# 8266_NFC_reader_added_power.net
KiCad netlist of a schematic drawn in EasyEDA
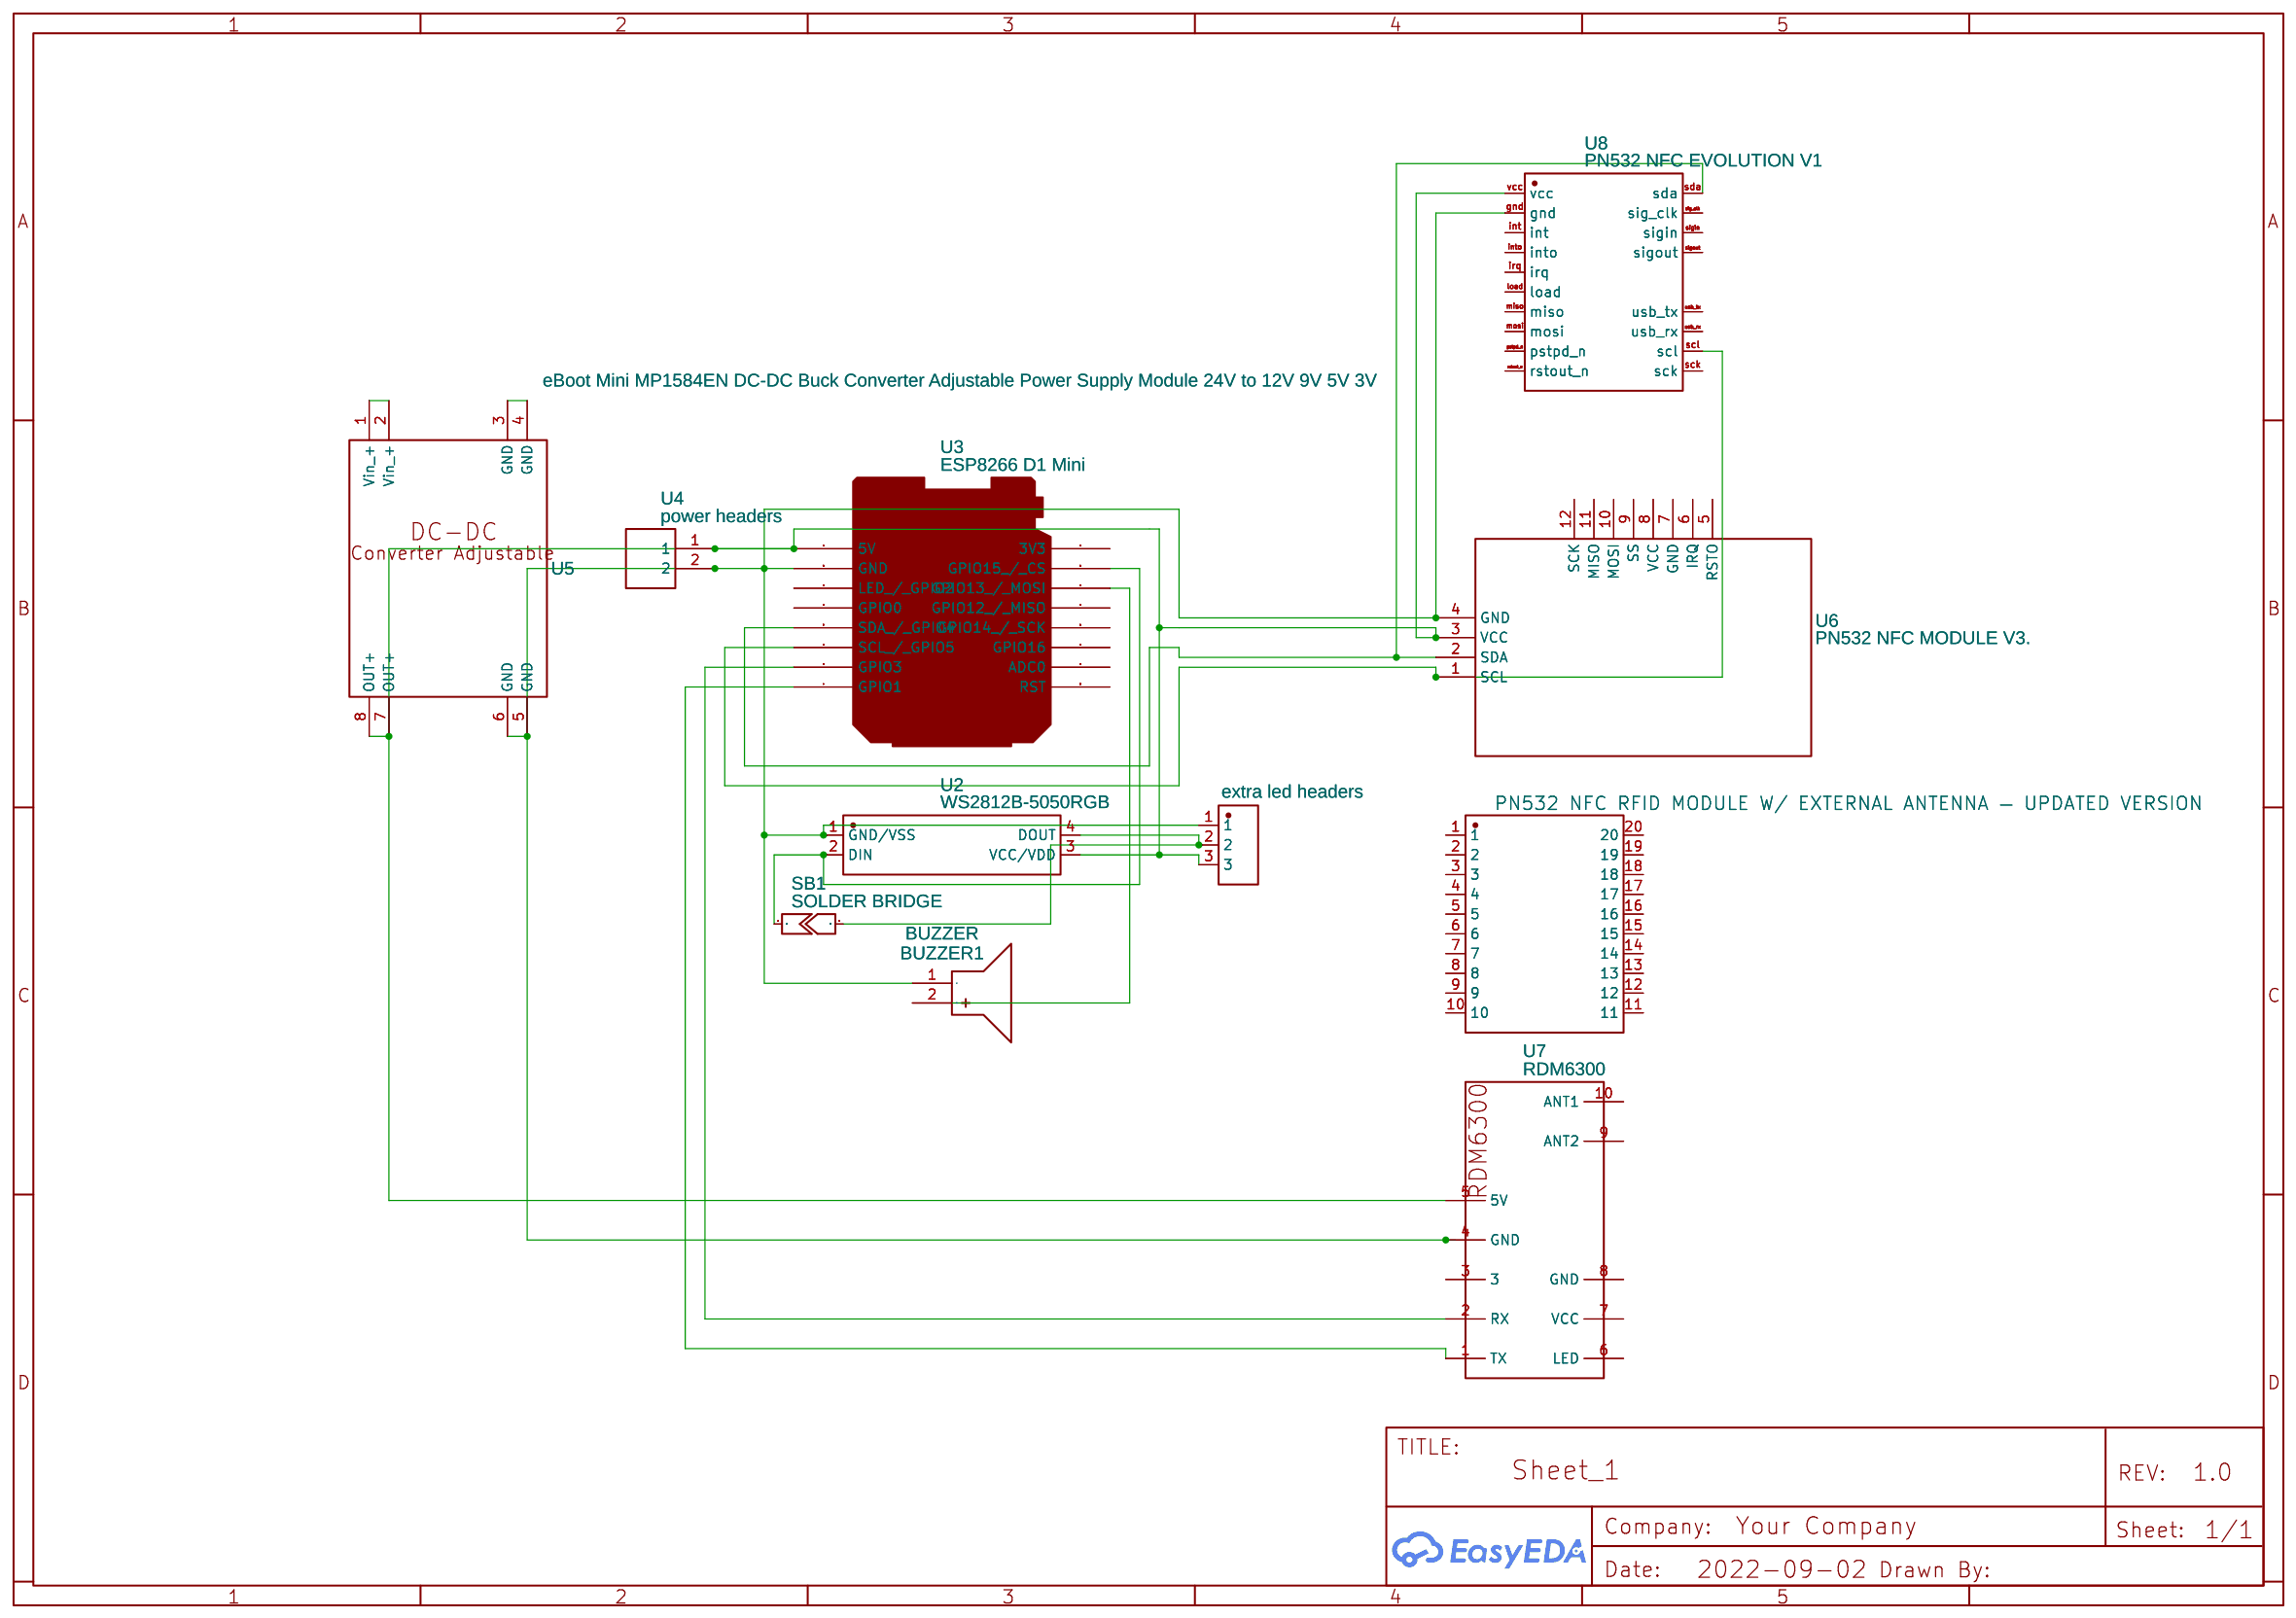
[diagram p0: schematic sheet]

(export (version "E")
  (design (tool "Eeschema 10.0.6"))
  (components
    (comp (ref "1")
      (value "extra led headers")
      (libsource (lib "") (part "PN532 NFC RFID MODULE W/ EXTERNAL ANTENNA — UPDATED VERSION"))
    )
    (comp (ref "BUZZER1")
      (value "BUZZER")
      (fields
        (field (name "BOM_Manufacturer Part") "buzzer")
        (field (name "BOM_Supplier Part") "C9900014030")
      )
      (libsource (lib "") (part "BUZZER"))
    )
    (comp (ref "SB1") (value "SOLDER BRIDGE") (libsource (lib "") (part "SOLDER BRIDGE")))
    (comp (ref "U2")
      (value "WS2812B-5050RGB")
      (fields (field (name "BOM_Supplier Part") "C2838584"))
      (libsource (lib "") (part "WS2812B-5050RGB"))
    )
    (comp (ref "U3") (value "ESP8266 D1 Mini") (libsource (lib "") (part "ESP8266 D1 Mini")))
    (comp (ref "U4")
      (value "power headers")
      (fields (field (name "BOM_Supplier Part") "7106"))
      (libsource (lib "") (part "1X2 HEADERS 2.54MM PITCH"))
    )
    (comp (ref "U5")
      (value "eBoot Mini MP1584EN DC-DC Buck Converter Adjustable Power Supply Module 24V to 12V 9V 5V 3V")
      (libsource (lib "") (part "eBoot Mini MP1584EN DC-DC Buck Converter Adjustable Power Supply Module 24V to 12V 9V 5V 3V"))
    )
    (comp (ref "U6") (value "PN532 NFC MODULE V3.") (libsource (lib "") (part "PN532 NFC MODULE V3.")))
    (comp (ref "U7") (value "RDM6300") (libsource (lib "") (part "RDM6300")))
    (comp (ref "U8") (value "PN532 NFC EVOLUTION V1") (libsource (lib "") (part "PN532 NFC EVOLUTION V1")))
  )
  (nets
    (net (code "1") (name "Net-(BUZZER1-+)") (class "Default")
      (node (ref "BUZZER1") (pin "2") (pinfunction "+_2") (pintype "unspecified"))
      (node (ref "U3") (pin "D7") (pinfunction "GPIO13_/_MOSI_D7") (pintype "bidirectional"))
    )
    (net (code "2") (name "Net-(BUZZER1--)") (class "Default")
      (node (ref "1") (pin "1") (pinfunction "1_1") (pintype "unspecified"))
      (node (ref "BUZZER1") (pin "1") (pinfunction "-_1") (pintype "unspecified"))
      (node (ref "U2") (pin "1") (pinfunction "GND/VSS_1") (pintype "unspecified"))
      (node (ref "U3") (pin "GND") (pinfunction "GND_GND") (pintype "passive"))
      (node (ref "U4") (pin "2") (pinfunction "2_2") (pintype "unspecified"))
      (node (ref "U5") (pin "5") (pinfunction "GND_5") (pintype "unspecified"))
      (node (ref "U5") (pin "6") (pinfunction "GND_6") (pintype "unspecified"))
      (node (ref "U6") (pin "4") (pinfunction "GND_4") (pintype "unspecified"))
      (node (ref "U7") (pin "4") (pinfunction "GND_4") (pintype "unspecified"))
      (node (ref "U8") (pin "gnd") (pinfunction "gnd_gnd") (pintype "unspecified"))
    )
    (net (code "3") (name "Net-(U2-DIN)") (class "Default")
      (node (ref "SB1") (pin "1") (pinfunction "1_1") (pintype "unspecified"))
      (node (ref "U2") (pin "2") (pinfunction "DIN_2") (pintype "unspecified"))
      (node (ref "U3") (pin "D8") (pinfunction "GPIO15_/_CS_D8") (pintype "bidirectional"))
    )
    (net (code "4") (name "Net-(U2-DOUT)") (class "Default")
      (node (ref "1") (pin "2") (pinfunction "2_2") (pintype "unspecified"))
      (node (ref "SB1") (pin "2") (pinfunction "2_2") (pintype "unspecified"))
      (node (ref "U2") (pin "4") (pinfunction "DOUT_4") (pintype "unspecified"))
    )
    (net (code "5") (name "Net-(U2-VCC{slash}VDD)") (class "Default")
      (node (ref "1") (pin "3") (pinfunction "3_3") (pintype "unspecified"))
      (node (ref "U2") (pin "3") (pinfunction "VCC/VDD_3") (pintype "unspecified"))
      (node (ref "U3") (pin "5V") (pinfunction "5V_5V") (pintype "passive"))
      (node (ref "U4") (pin "1") (pinfunction "1_1") (pintype "unspecified"))
      (node (ref "U5") (pin "7") (pinfunction "OUT+_7") (pintype "unspecified"))
      (node (ref "U5") (pin "8") (pinfunction "OUT+_8") (pintype "unspecified"))
      (node (ref "U6") (pin "3") (pinfunction "VCC_3") (pintype "unspecified"))
      (node (ref "U7") (pin "5") (pinfunction "5V_5") (pintype "unspecified"))
      (node (ref "U8") (pin "vcc") (pinfunction "vcc_vcc") (pintype "unspecified"))
    )
    (net (code "6") (name "Net-(U3-GPIO1)") (class "Default")
      (node (ref "U3") (pin "TX") (pinfunction "GPIO1_TX") (pintype "bidirectional"))
      (node (ref "U7") (pin "1") (pinfunction "TX_1") (pintype "unspecified"))
    )
    (net (code "7") (name "Net-(U3-GPIO3)") (class "Default")
      (node (ref "U3") (pin "RX") (pinfunction "GPIO3_RX") (pintype "bidirectional"))
      (node (ref "U7") (pin "2") (pinfunction "RX_2") (pintype "unspecified"))
    )
    (net (code "8") (name "Net-(U3-SCL_{slash}_GPIO5)") (class "Default")
      (node (ref "U3") (pin "D1") (pinfunction "SCL_/_GPIO5_D1") (pintype "bidirectional"))
      (node (ref "U6") (pin "1") (pinfunction "SCL_1") (pintype "unspecified"))
      (node (ref "U8") (pin "scl") (pinfunction "scl_scl") (pintype "unspecified"))
    )
    (net (code "9") (name "Net-(U3-SDA_{slash}_GPIO4)") (class "Default")
      (node (ref "U3") (pin "D2") (pinfunction "SDA_/_GPIO4_D2") (pintype "bidirectional"))
      (node (ref "U6") (pin "2") (pinfunction "SDA_2") (pintype "unspecified"))
      (node (ref "U8") (pin "sda") (pinfunction "sda_sda") (pintype "unspecified"))
    )
    (net (code "10") (name "Net-(U5-GND-Pad3)") (class "Default")
      (node (ref "U5") (pin "3") (pinfunction "GND_3") (pintype "unspecified"))
      (node (ref "U5") (pin "4") (pinfunction "GND_4") (pintype "unspecified"))
    )
    (net (code "11") (name "Net-(U5-Vin_+-Pad1)") (class "Default")
      (node (ref "U5") (pin "1") (pinfunction "Vin_+_1") (pintype "unspecified"))
      (node (ref "U5") (pin "2") (pinfunction "Vin_+_2") (pintype "unspecified"))
    )
    (net (code "12") (name "unconnected-(1-Pad1)") (class "Default")
      (node (ref "1") (pin "1") (pinfunction "1_1") (pintype "unspecified"))
    )
    (net (code "13") (name "unconnected-(1-Pad2)") (class "Default")
      (node (ref "1") (pin "2") (pinfunction "2_2") (pintype "unspecified"))
    )
    (net (code "14") (name "unconnected-(1-Pad3)") (class "Default")
      (node (ref "1") (pin "3") (pinfunction "3_3") (pintype "unspecified"))
    )
    (net (code "15") (name "unconnected-(1-Pad4)") (class "Default")
      (node (ref "1") (pin "4") (pinfunction "4_4") (pintype "unspecified"))
    )
    (net (code "16") (name "unconnected-(1-Pad5)") (class "Default")
      (node (ref "1") (pin "5") (pinfunction "5_5") (pintype "unspecified"))
    )
    (net (code "17") (name "unconnected-(1-Pad6)") (class "Default")
      (node (ref "1") (pin "6") (pinfunction "6_6") (pintype "unspecified"))
    )
    (net (code "18") (name "unconnected-(1-Pad7)") (class "Default")
      (node (ref "1") (pin "7") (pinfunction "7_7") (pintype "unspecified"))
    )
    (net (code "19") (name "unconnected-(1-Pad8)") (class "Default")
      (node (ref "1") (pin "8") (pinfunction "8_8") (pintype "unspecified"))
    )
    (net (code "20") (name "unconnected-(1-Pad9)") (class "Default")
      (node (ref "1") (pin "9") (pinfunction "9_9") (pintype "unspecified"))
    )
    (net (code "21") (name "unconnected-(1-Pad10)") (class "Default")
      (node (ref "1") (pin "10") (pinfunction "10_10") (pintype "unspecified"))
    )
    (net (code "22") (name "unconnected-(1-Pad11)") (class "Default")
      (node (ref "1") (pin "11") (pinfunction "11_11") (pintype "unspecified"))
    )
    (net (code "23") (name "unconnected-(1-Pad12)") (class "Default")
      (node (ref "1") (pin "12") (pinfunction "12_12") (pintype "unspecified"))
    )
    (net (code "24") (name "unconnected-(1-Pad13)") (class "Default")
      (node (ref "1") (pin "13") (pinfunction "13_13") (pintype "unspecified"))
    )
    (net (code "25") (name "unconnected-(1-Pad14)") (class "Default")
      (node (ref "1") (pin "14") (pinfunction "14_14") (pintype "unspecified"))
    )
    (net (code "26") (name "unconnected-(1-Pad15)") (class "Default")
      (node (ref "1") (pin "15") (pinfunction "15_15") (pintype "unspecified"))
    )
    (net (code "27") (name "unconnected-(1-Pad16)") (class "Default")
      (node (ref "1") (pin "16") (pinfunction "16_16") (pintype "unspecified"))
    )
    (net (code "28") (name "unconnected-(1-Pad17)") (class "Default")
      (node (ref "1") (pin "17") (pinfunction "17_17") (pintype "unspecified"))
    )
    (net (code "29") (name "unconnected-(1-Pad18)") (class "Default")
      (node (ref "1") (pin "18") (pinfunction "18_18") (pintype "unspecified"))
    )
    (net (code "30") (name "unconnected-(1-Pad19)") (class "Default")
      (node (ref "1") (pin "19") (pinfunction "19_19") (pintype "unspecified"))
    )
    (net (code "31") (name "unconnected-(1-Pad20)") (class "Default")
      (node (ref "1") (pin "20") (pinfunction "20_20") (pintype "unspecified"))
    )
    (net (code "32") (name "unconnected-(U3-ADC0-PadA0)") (class "Default")
      (node (ref "U3") (pin "A0") (pinfunction "ADC0_A0") (pintype "input"))
    )
    (net (code "33") (name "unconnected-(U3-GPIO0-PadD3)") (class "Default")
      (node (ref "U3") (pin "D3") (pinfunction "GPIO0_D3") (pintype "bidirectional"))
    )
    (net (code "34") (name "unconnected-(U3-GPIO12_{slash}_MISO-PadD6)") (class "Default")
      (node (ref "U3") (pin "D6") (pinfunction "GPIO12_/_MISO_D6") (pintype "bidirectional"))
    )
    (net (code "35") (name "unconnected-(U3-GPIO14_{slash}_SCK-PadD5)") (class "Default")
      (node (ref "U3") (pin "D5") (pinfunction "GPIO14_/_SCK_D5") (pintype "bidirectional"))
    )
    (net (code "36") (name "unconnected-(U3-GPIO16-PadD0)") (class "Default")
      (node (ref "U3") (pin "D0") (pinfunction "GPIO16_D0") (pintype "bidirectional"))
    )
    (net (code "37") (name "unconnected-(U3-LED_{slash}_GPIO2-PadD4)") (class "Default")
      (node (ref "U3") (pin "D4") (pinfunction "LED_/_GPIO2_D4") (pintype "bidirectional"))
    )
    (net (code "38") (name "unconnected-(U3-Pad3V3)") (class "Default")
      (node (ref "U3") (pin "3V3") (pinfunction "3V3_3V3") (pintype "passive"))
    )
    (net (code "39") (name "unconnected-(U3-PadRST)") (class "Default")
      (node (ref "U3") (pin "RST") (pinfunction "RST_RST") (pintype "input"))
    )
    (net (code "40") (name "unconnected-(U6-GND-Pad7)") (class "Default")
      (node (ref "U6") (pin "7") (pinfunction "GND_7") (pintype "unspecified"))
    )
    (net (code "41") (name "unconnected-(U6-IRQ-Pad6)") (class "Default")
      (node (ref "U6") (pin "6") (pinfunction "IRQ_6") (pintype "unspecified"))
    )
    (net (code "42") (name "unconnected-(U6-MISO-Pad11)") (class "Default")
      (node (ref "U6") (pin "11") (pinfunction "MISO_11") (pintype "unspecified"))
    )
    (net (code "43") (name "unconnected-(U6-MOSI-Pad10)") (class "Default")
      (node (ref "U6") (pin "10") (pinfunction "MOSI_10") (pintype "unspecified"))
    )
    (net (code "44") (name "unconnected-(U6-RSTO-Pad5)") (class "Default")
      (node (ref "U6") (pin "5") (pinfunction "RSTO_5") (pintype "unspecified"))
    )
    (net (code "45") (name "unconnected-(U6-SCK-Pad12)") (class "Default")
      (node (ref "U6") (pin "12") (pinfunction "SCK_12") (pintype "unspecified"))
    )
    (net (code "46") (name "unconnected-(U6-SS-Pad9)") (class "Default")
      (node (ref "U6") (pin "9") (pinfunction "SS_9") (pintype "unspecified"))
    )
    (net (code "47") (name "unconnected-(U6-VCC-Pad8)") (class "Default")
      (node (ref "U6") (pin "8") (pinfunction "VCC_8") (pintype "unspecified"))
    )
    (net (code "48") (name "unconnected-(U7-ANT1-Pad10)") (class "Default")
      (node (ref "U7") (pin "10") (pinfunction "ANT1_10") (pintype "unspecified"))
    )
    (net (code "49") (name "unconnected-(U7-ANT2-Pad9)") (class "Default")
      (node (ref "U7") (pin "9") (pinfunction "ANT2_9") (pintype "unspecified"))
    )
    (net (code "50") (name "unconnected-(U7-GND-Pad8)") (class "Default")
      (node (ref "U7") (pin "8") (pinfunction "GND_8") (pintype "unspecified"))
    )
    (net (code "51") (name "unconnected-(U7-LED-Pad6)") (class "Default")
      (node (ref "U7") (pin "6") (pinfunction "LED_6") (pintype "unspecified"))
    )
    (net (code "52") (name "unconnected-(U7-Pad3)") (class "Default")
      (node (ref "U7") (pin "3") (pinfunction "3_3") (pintype "unspecified"))
    )
    (net (code "53") (name "unconnected-(U7-VCC-Pad7)") (class "Default")
      (node (ref "U7") (pin "7") (pinfunction "VCC_7") (pintype "unspecified"))
    )
    (net (code "54") (name "unconnected-(U8-Padint)") (class "Default")
      (node (ref "U8") (pin "int") (pinfunction "int_int") (pintype "unspecified"))
    )
    (net (code "55") (name "unconnected-(U8-Padinto)") (class "Default")
      (node (ref "U8") (pin "into") (pinfunction "into_into") (pintype "unspecified"))
    )
    (net (code "56") (name "unconnected-(U8-Padirq)") (class "Default")
      (node (ref "U8") (pin "irq") (pinfunction "irq_irq") (pintype "unspecified"))
    )
    (net (code "57") (name "unconnected-(U8-Padload)") (class "Default")
      (node (ref "U8") (pin "load") (pinfunction "load_load") (pintype "unspecified"))
    )
    (net (code "58") (name "unconnected-(U8-Padmiso)") (class "Default")
      (node (ref "U8") (pin "miso") (pinfunction "miso_miso") (pintype "unspecified"))
    )
    (net (code "59") (name "unconnected-(U8-Padmosi)") (class "Default")
      (node (ref "U8") (pin "mosi") (pinfunction "mosi_mosi") (pintype "unspecified"))
    )
    (net (code "60") (name "unconnected-(U8-Padpstpd_n)") (class "Default")
      (node (ref "U8") (pin "pstpd_n") (pinfunction "pstpd_n_pstpd_n") (pintype "unspecified"))
    )
    (net (code "61") (name "unconnected-(U8-Padrstout_n)") (class "Default")
      (node (ref "U8") (pin "rstout_n") (pinfunction "rstout_n_rstout_n") (pintype "unspecified"))
    )
    (net (code "62") (name "unconnected-(U8-Padsck)") (class "Default")
      (node (ref "U8") (pin "sck") (pinfunction "sck_sck") (pintype "unspecified"))
    )
    (net (code "63") (name "unconnected-(U8-Padsig_clk)") (class "Default")
      (node (ref "U8") (pin "sig_clk") (pinfunction "sig_clk_sig_clk") (pintype "unspecified"))
    )
    (net (code "64") (name "unconnected-(U8-Padsigin)") (class "Default")
      (node (ref "U8") (pin "sigin") (pinfunction "sigin_sigin") (pintype "unspecified"))
    )
    (net (code "65") (name "unconnected-(U8-Padsigout)") (class "Default")
      (node (ref "U8") (pin "sigout") (pinfunction "sigout_sigout") (pintype "unspecified"))
    )
    (net (code "66") (name "unconnected-(U8-Padusb_rx)") (class "Default")
      (node (ref "U8") (pin "usb_rx") (pinfunction "usb_rx_usb_rx") (pintype "unspecified"))
    )
    (net (code "67") (name "unconnected-(U8-Padusb_tx)") (class "Default")
      (node (ref "U8") (pin "usb_tx") (pinfunction "usb_tx_usb_tx") (pintype "unspecified"))
    )
  )
)
